# SensWear_Touch.net
KiCad netlist of a schematic drawn in Altium Designer
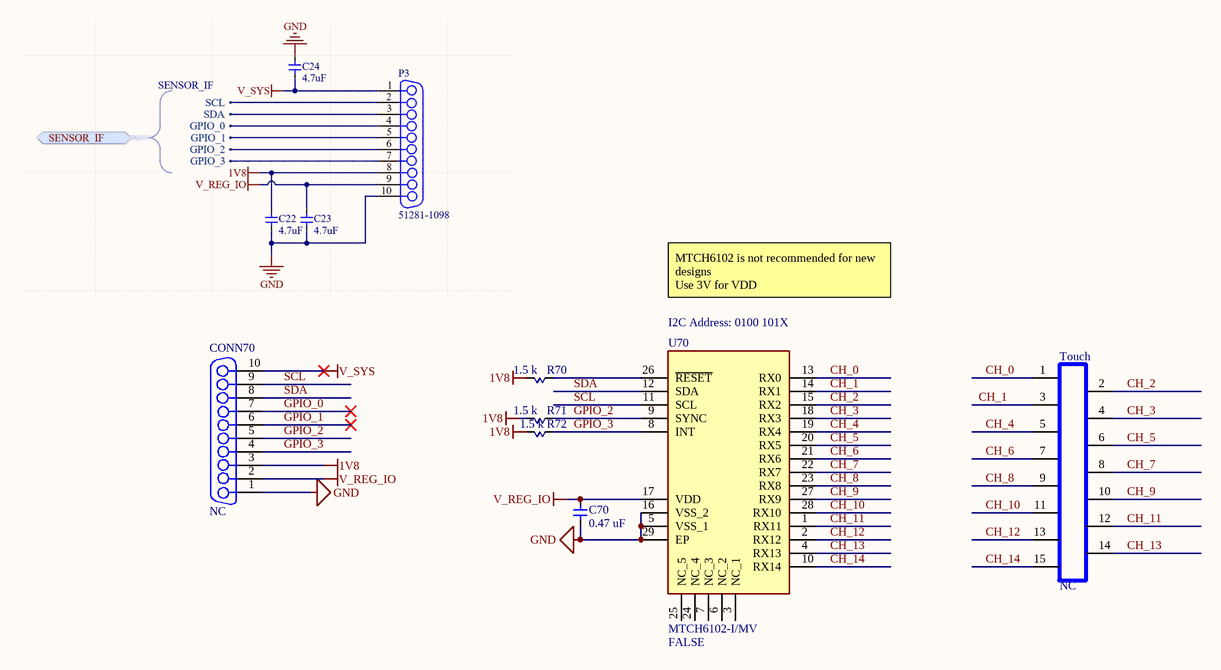
[diagram p0: SensWear_Touch.SchDoc]

(export (version "E")
  (design (tool "Eeschema 10.0.6"))
  (components
    (comp (ref "C70")
      (value "0.47 uF")
      (footprint "CAPC1005X05N")
      (description "CAP CER 0.47UF 10V X5R 0402")
      (fields
        (field (name "MANUFACTURER") "Murata Electronics North America")
        (field (name "MANUFACTURER PART NUMBER") "GRM155R61A474KE15D")
      )
      (libsource (lib "OpenRingComponents") (part "GRM155R61A474KE15D"))
    )
    (comp (ref "CONN70")
      (value "NC")
      (footprint "51281-1098-PCB")
      (libsource (lib "Connectors") (part "51281-1098-PCB"))
    )
    (comp (ref "R70")
      (value "1.5 k")
      (footprint "RESC1005X04N")
      (description "RES SMD 1.5K OHM 1% 1/10W 0402")
      (fields
        (field (name "MANUFACTURER") "Panasonic Electronic Components")
        (field (name "MANUFACTURER PART NUMBER") "ERJ-2RKF1501X")
      )
      (libsource (lib "OpenRingComponents") (part "ERJ-2RKF1501X"))
    )
    (comp (ref "R71")
      (value "1.5 k")
      (footprint "RESC1005X04N")
      (description "RES SMD 1.5K OHM 1% 1/10W 0402")
      (fields
        (field (name "MANUFACTURER") "Panasonic Electronic Components")
        (field (name "MANUFACTURER PART NUMBER") "ERJ-2RKF1501X")
      )
      (libsource (lib "OpenRingComponents") (part "ERJ-2RKF1501X"))
    )
    (comp (ref "R72")
      (value "1.5 k")
      (footprint "RESC1005X04N")
      (description "RES SMD 1.5K OHM 1% 1/10W 0402")
      (fields
        (field (name "MANUFACTURER") "Panasonic Electronic Components")
        (field (name "MANUFACTURER PART NUMBER") "ERJ-2RKF1501X")
      )
      (libsource (lib "OpenRingComponents") (part "ERJ-2RKF1501X"))
    )
    (comp (ref "Touch")
      (value "NC")
      (footprint "Touch-15Ch-Linear")
      (libsource (lib "OpenRingComponents") (part "Touch-15Ch-Linear"))
    )
    (comp (ref "U70")
      (value "MTCH6102-I/MV")
      (footprint "QFN40P400X400X55_HS-29N")
      (description "Capacitive Touch Screen Automotive 28-Pin UQFN EP Tube")
      (fields (field (name "MANUFACTURER") "Microchip") (field (name "CHECKED") "FALSE"))
      (libsource (lib "OpenRingComponents") (part "MTCH6102-I/MV"))
    )
  )
  (nets
    (net (code "1") (name "/CH_0") (class "Default")
      (node (ref "Touch") (pin "1") (pinfunction "1_1") (pintype "passive"))
      (node (ref "U70") (pin "13") (pinfunction "RX0_13") (pintype "passive"))
    )
    (net (code "2") (name "/CH_1") (class "Default")
      (node (ref "Touch") (pin "3") (pinfunction "3_3") (pintype "passive"))
      (node (ref "U70") (pin "14") (pinfunction "RX1_14") (pintype "passive"))
    )
    (net (code "3") (name "/CH_2") (class "Default")
      (node (ref "Touch") (pin "2") (pinfunction "2_2") (pintype "passive"))
      (node (ref "U70") (pin "15") (pinfunction "RX2_15") (pintype "passive"))
    )
    (net (code "4") (name "/CH_3") (class "Default")
      (node (ref "Touch") (pin "4") (pinfunction "4_4") (pintype "passive"))
      (node (ref "U70") (pin "18") (pinfunction "RX3_18") (pintype "passive"))
    )
    (net (code "5") (name "/CH_4") (class "Default")
      (node (ref "Touch") (pin "5") (pinfunction "5_5") (pintype "passive"))
      (node (ref "U70") (pin "19") (pinfunction "RX4_19") (pintype "passive"))
    )
    (net (code "6") (name "/CH_5") (class "Default")
      (node (ref "Touch") (pin "6") (pinfunction "6_6") (pintype "passive"))
      (node (ref "U70") (pin "20") (pinfunction "RX5_20") (pintype "passive"))
    )
    (net (code "7") (name "/CH_6") (class "Default")
      (node (ref "Touch") (pin "7") (pinfunction "7_7") (pintype "passive"))
      (node (ref "U70") (pin "21") (pinfunction "RX6_21") (pintype "passive"))
    )
    (net (code "8") (name "/CH_7") (class "Default")
      (node (ref "Touch") (pin "8") (pinfunction "8_8") (pintype "passive"))
      (node (ref "U70") (pin "22") (pinfunction "RX7_22") (pintype "passive"))
    )
    (net (code "9") (name "/CH_8") (class "Default")
      (node (ref "Touch") (pin "9") (pinfunction "9_9") (pintype "passive"))
      (node (ref "U70") (pin "23") (pinfunction "RX8_23") (pintype "passive"))
    )
    (net (code "10") (name "/CH_9") (class "Default")
      (node (ref "Touch") (pin "10") (pinfunction "10_10") (pintype "passive"))
      (node (ref "U70") (pin "27") (pinfunction "RX9_27") (pintype "passive"))
    )
    (net (code "11") (name "/CH_10") (class "Default")
      (node (ref "Touch") (pin "11") (pinfunction "11_11") (pintype "passive"))
      (node (ref "U70") (pin "28") (pinfunction "RX10_28") (pintype "passive"))
    )
    (net (code "12") (name "/CH_11") (class "Default")
      (node (ref "Touch") (pin "12") (pinfunction "12_12") (pintype "passive"))
      (node (ref "U70") (pin "1") (pinfunction "RX11_1") (pintype "passive"))
    )
    (net (code "13") (name "/CH_12") (class "Default")
      (node (ref "Touch") (pin "13") (pinfunction "13_13") (pintype "passive"))
      (node (ref "U70") (pin "2") (pinfunction "RX12_2") (pintype "passive"))
    )
    (net (code "14") (name "/CH_13") (class "Default")
      (node (ref "Touch") (pin "14") (pinfunction "14_14") (pintype "passive"))
      (node (ref "U70") (pin "4") (pinfunction "RX13_4") (pintype "passive"))
    )
    (net (code "15") (name "/CH_14") (class "Default")
      (node (ref "Touch") (pin "15") (pinfunction "15_15") (pintype "passive"))
      (node (ref "U70") (pin "10") (pinfunction "RX14_10") (pintype "passive"))
    )
    (net (code "16") (name "/GPIO_0") (class "Default")
      (node (ref "CONN70") (pin "7") (pinfunction "7_7") (pintype "passive+no_connect"))
    )
    (net (code "17") (name "/GPIO_1") (class "Default")
      (node (ref "CONN70") (pin "6") (pinfunction "6_6") (pintype "passive+no_connect"))
    )
    (net (code "18") (name "/GPIO_2") (class "Default")
      (node (ref "CONN70") (pin "5") (pinfunction "5_5") (pintype "passive"))
      (node (ref "R71") (pin "1") (pinfunction "1_1") (pintype "passive"))
      (node (ref "U70") (pin "9") (pinfunction "SYNC_9") (pintype "passive"))
    )
    (net (code "19") (name "/GPIO_3") (class "Default")
      (node (ref "CONN70") (pin "4") (pinfunction "4_4") (pintype "passive"))
      (node (ref "R72") (pin "1") (pinfunction "1_1") (pintype "passive"))
      (node (ref "U70") (pin "8") (pinfunction "INT_8") (pintype "passive"))
    )
    (net (code "20") (name "/SCL") (class "Default")
      (node (ref "CONN70") (pin "9") (pinfunction "9_9") (pintype "passive"))
      (node (ref "U70") (pin "11") (pinfunction "SCL_11") (pintype "passive"))
    )
    (net (code "21") (name "/SDA") (class "Default")
      (node (ref "CONN70") (pin "8") (pinfunction "8_8") (pintype "passive"))
      (node (ref "U70") (pin "12") (pinfunction "SDA_12") (pintype "passive"))
    )
    (net (code "22") (name "1V8") (class "Default")
      (node (ref "CONN70") (pin "3") (pinfunction "3_3") (pintype "passive"))
      (node (ref "R70") (pin "2") (pinfunction "2_2") (pintype "passive"))
      (node (ref "R71") (pin "2") (pinfunction "2_2") (pintype "passive"))
      (node (ref "R72") (pin "2") (pinfunction "2_2") (pintype "passive"))
    )
    (net (code "23") (name "GND") (class "Default")
      (node (ref "C70") (pin "2") (pinfunction "2_2") (pintype "passive"))
      (node (ref "CONN70") (pin "1") (pinfunction "1_1") (pintype "passive"))
      (node (ref "U70") (pin "16") (pinfunction "VSS_2_16") (pintype "passive"))
      (node (ref "U70") (pin "29") (pinfunction "EP_29") (pintype "passive"))
      (node (ref "U70") (pin "5") (pinfunction "VSS_1_5") (pintype "passive"))
    )
    (net (code "24") (name "Net-(U70-~{RESET})") (class "Default")
      (node (ref "R70") (pin "1") (pinfunction "1_1") (pintype "passive"))
      (node (ref "U70") (pin "26") (pinfunction "~{RESET}_26") (pintype "passive"))
    )
    (net (code "25") (name "V_REG_IO") (class "Default")
      (node (ref "C70") (pin "1") (pinfunction "1_1") (pintype "passive"))
      (node (ref "CONN70") (pin "2") (pinfunction "2_2") (pintype "passive"))
      (node (ref "U70") (pin "17") (pinfunction "VDD_17") (pintype "passive"))
    )
    (net (code "26") (name "V_SYS") (class "Default")
      (node (ref "CONN70") (pin "10") (pinfunction "10_10") (pintype "passive"))
    )
    (net (code "27") (name "unconnected-(U70-NC_1-Pad3)") (class "Default")
      (node (ref "U70") (pin "3") (pinfunction "NC_1_3") (pintype "passive"))
    )
    (net (code "28") (name "unconnected-(U70-NC_2-Pad6)") (class "Default")
      (node (ref "U70") (pin "6") (pinfunction "NC_2_6") (pintype "passive"))
    )
    (net (code "29") (name "unconnected-(U70-NC_3-Pad7)") (class "Default")
      (node (ref "U70") (pin "7") (pinfunction "NC_3_7") (pintype "passive"))
    )
    (net (code "30") (name "unconnected-(U70-NC_4-Pad24)") (class "Default")
      (node (ref "U70") (pin "24") (pinfunction "NC_4_24") (pintype "passive"))
    )
    (net (code "31") (name "unconnected-(U70-NC_5-Pad25)") (class "Default")
      (node (ref "U70") (pin "25") (pinfunction "NC_5_25") (pintype "passive"))
    )
  )
)
